# RF_And_SD_Ticketing_Master.net
KiCad netlist of a schematic drawn in Altium Designer
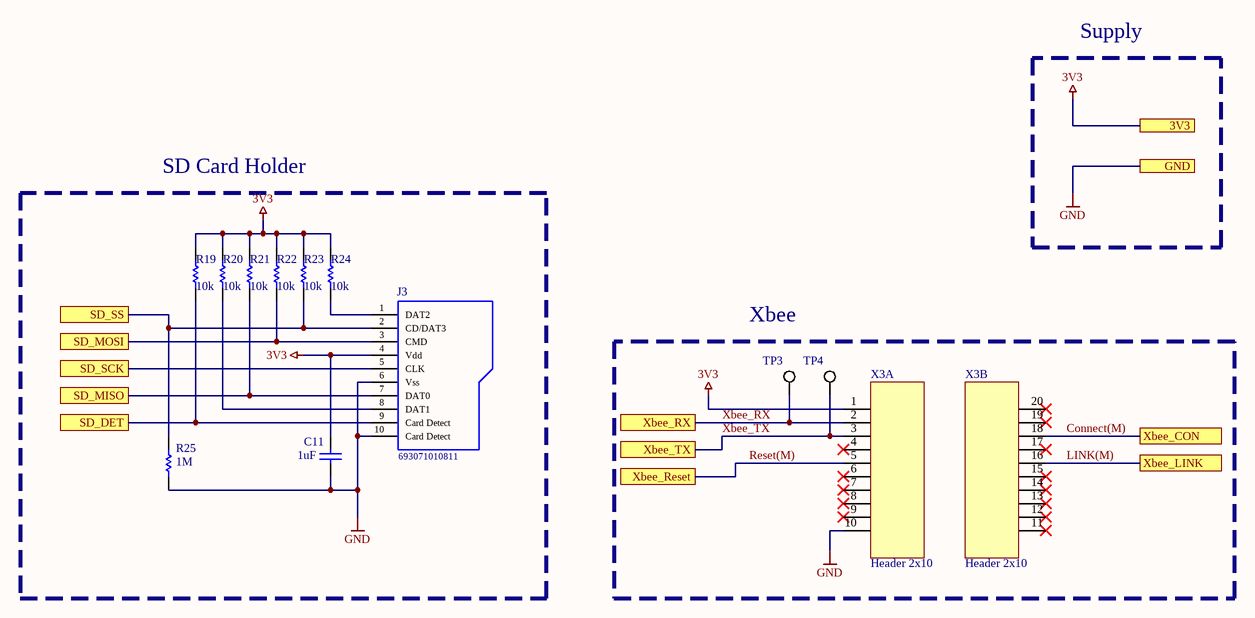
[diagram p0: RF_And_SD_Ticketing_Master.SchDoc]

(export (version "E")
  (design (tool "Eeschema 10.0.6"))
  (components
    (comp (ref "C11")
      (value "1uF")
      (footprint "6-0805_N")
      (description "Capacitor")
      (fields (field (name "PUBLISHER") "Altium Limited"))
      (libsource (lib "Miscellaneous Devices") (part "Cap"))
    )
    (comp (ref "J3")
      (value "693071010811")
      (footprint "693071010811")
      (description "WR-CRD Micro SD Card Connector, Push & Push, with card detection")
      (fields (field (name "PART NUMBER") "732-3819-1-ND") (field (name "PUBLISHER") "Wurth Elektronik"))
      (libsource (lib "ALTIUM-WR-CRD-rev18a") (part "693071010811"))
    )
    (comp (ref "R19")
      (value "10k")
      (footprint "RESC0805(2012)_L")
      (description "100K 0.125W 5% 0805 (2012 Metric)  SMD")
      (fields (field (name "TOLERANCE") "5 %") (field (name "POWER") "0.125 W"))
      (libsource (lib "Altium Content Vault") (part "CMP-1013-00122-1"))
    )
    (comp (ref "R20")
      (value "10k")
      (footprint "RESC0805(2012)_L")
      (description "100K 0.125W 5% 0805 (2012 Metric)  SMD")
      (fields (field (name "TOLERANCE") "5 %") (field (name "POWER") "0.125 W"))
      (libsource (lib "Altium Content Vault") (part "CMP-1013-00122-1"))
    )
    (comp (ref "R21")
      (value "10k")
      (footprint "RESC0805(2012)_L")
      (description "100K 0.125W 5% 0805 (2012 Metric)  SMD")
      (fields (field (name "TOLERANCE") "5 %") (field (name "POWER") "0.125 W"))
      (libsource (lib "Altium Content Vault") (part "CMP-1013-00122-1"))
    )
    (comp (ref "R22")
      (value "10k")
      (footprint "RESC0805(2012)_L")
      (description "100K 0.125W 5% 0805 (2012 Metric)  SMD")
      (fields (field (name "TOLERANCE") "5 %") (field (name "POWER") "0.125 W"))
      (libsource (lib "Altium Content Vault") (part "CMP-1013-00122-1"))
    )
    (comp (ref "R23")
      (value "10k")
      (footprint "RESC0805(2012)_L")
      (description "100K 0.125W 5% 0805 (2012 Metric)  SMD")
      (fields (field (name "TOLERANCE") "5 %") (field (name "POWER") "0.125 W"))
      (libsource (lib "Altium Content Vault") (part "CMP-1013-00122-1"))
    )
    (comp (ref "R24")
      (value "10k")
      (footprint "RESC0805(2012)_L")
      (description "100K 0.125W 5% 0805 (2012 Metric)  SMD")
      (fields (field (name "TOLERANCE") "5 %") (field (name "POWER") "0.125 W"))
      (libsource (lib "Altium Content Vault") (part "CMP-1013-00122-1"))
    )
    (comp (ref "R25")
      (value "1M")
      (footprint "RESC0805(2012)_L")
      (description "100K 0.125W 5% 0805 (2012 Metric)  SMD")
      (fields (field (name "TOLERANCE") "5 %") (field (name "POWER") "0.125 W"))
      (libsource (lib "Altium Content Vault") (part "CMP-1013-00122-1"))
    )
    (comp (ref "TP3")
      (value "~")
      (footprint "KSTN-5019_V")
      (description "Test Point, 1 Position SMD, RoHS, Tape and Reel")
      (libsource (lib "Altium Content Vault") (part "TESTPOINT_WHITE"))
    )
    (comp (ref "TP4")
      (value "~")
      (footprint "KSTN-5019_V")
      (description "Test Point, 1 Position SMD, RoHS, Tape and Reel")
      (libsource (lib "Altium Content Vault") (part "TESTPOINT_WHITE"))
    )
    (comp (ref "X3")
      (value "Header 2x10")
      (footprint "ZB-SB")
      (description "Header 2x10\r\nXbee de letml(1623) ou xbee XB24CAUIT-001")
      (libsource (lib "PCB_Ticketing_Master") (part "HDR ZB-SB 2x10_1"))
    )
  )
  (nets
    (net (code "1") (name "/Connect(M)") (class "Default") (node (ref "X3") (pin "18") (pintype "passive")))
    (net (code "2") (name "/LINK(M)") (class "Default") (node (ref "X3") (pin "16") (pintype "passive")))
    (net (code "3") (name "/Reset(M)") (class "Default") (node (ref "X3") (pin "5") (pintype "passive")))
    (net (code "4") (name "/SD_DET") (class "Default")
      (node (ref "J3") (pin "9") (pinfunction "Card_Detect_9") (pintype "passive"))
      (node (ref "R19") (pin "1") (pinfunction "1_1") (pintype "passive"))
    )
    (net (code "5") (name "/SD_MISO") (class "Default")
      (node (ref "J3") (pin "7") (pinfunction "DAT0_7") (pintype "passive"))
      (node (ref "R21") (pin "1") (pinfunction "1_1") (pintype "passive"))
    )
    (net (code "6") (name "/SD_MOSI") (class "Default")
      (node (ref "J3") (pin "3") (pinfunction "CMD_3") (pintype "passive"))
      (node (ref "R22") (pin "1") (pinfunction "1_1") (pintype "passive"))
    )
    (net (code "7") (name "/SD_SCK") (class "Default")
      (node (ref "J3") (pin "5") (pinfunction "CLK_5") (pintype "passive"))
    )
    (net (code "8") (name "/SD_SS") (class "Default")
      (node (ref "J3") (pin "2") (pinfunction "CD/DAT3_2") (pintype "passive"))
      (node (ref "R23") (pin "1") (pinfunction "1_1") (pintype "passive"))
      (node (ref "R25") (pin "2") (pinfunction "2_2") (pintype "passive"))
    )
    (net (code "9") (name "/Xbee_RX") (class "Default")
      (node (ref "TP3") (pin "1") (pinfunction "1_1") (pintype "passive"))
      (node (ref "X3") (pin "2") (pintype "passive"))
    )
    (net (code "10") (name "/Xbee_TX") (class "Default")
      (node (ref "TP4") (pin "1") (pinfunction "1_1") (pintype "passive"))
      (node (ref "X3") (pin "3") (pintype "passive"))
    )
    (net (code "11") (name "3V3") (class "Default")
      (node (ref "C11") (pin "2") (pinfunction "2_2") (pintype "passive"))
      (node (ref "J3") (pin "4") (pinfunction "Vdd_4") (pintype "passive"))
      (node (ref "R19") (pin "2") (pinfunction "2_2") (pintype "passive"))
      (node (ref "R20") (pin "2") (pinfunction "2_2") (pintype "passive"))
      (node (ref "R21") (pin "2") (pinfunction "2_2") (pintype "passive"))
      (node (ref "R22") (pin "2") (pinfunction "2_2") (pintype "passive"))
      (node (ref "R23") (pin "2") (pinfunction "2_2") (pintype "passive"))
      (node (ref "R24") (pin "2") (pinfunction "2_2") (pintype "passive"))
      (node (ref "X3") (pin "1") (pintype "passive"))
    )
    (net (code "12") (name "GND") (class "Default")
      (node (ref "C11") (pin "1") (pinfunction "1_1") (pintype "passive"))
      (node (ref "J3") (pin "10") (pinfunction "Card_Detect_10") (pintype "passive"))
      (node (ref "J3") (pin "6") (pinfunction "Vss_6") (pintype "passive"))
      (node (ref "R25") (pin "1") (pinfunction "1_1") (pintype "passive"))
      (node (ref "X3") (pin "10") (pintype "passive"))
    )
    (net (code "13") (name "Net-(J3-DAT1)") (class "Default")
      (node (ref "J3") (pin "8") (pinfunction "DAT1_8") (pintype "passive"))
      (node (ref "R20") (pin "1") (pinfunction "1_1") (pintype "passive"))
    )
    (net (code "14") (name "Net-(J3-DAT2)") (class "Default")
      (node (ref "J3") (pin "1") (pinfunction "DAT2_1") (pintype "passive"))
      (node (ref "R24") (pin "1") (pinfunction "1_1") (pintype "passive"))
    )
    (net (code "15") (name "unconnected-(X3-Pad4)") (class "Default")
      (node (ref "X3") (pin "4") (pintype "passive+no_connect"))
    )
    (net (code "16") (name "unconnected-(X3-Pad6)") (class "Default")
      (node (ref "X3") (pin "6") (pintype "passive+no_connect"))
    )
    (net (code "17") (name "unconnected-(X3-Pad7)") (class "Default")
      (node (ref "X3") (pin "7") (pintype "passive+no_connect"))
    )
    (net (code "18") (name "unconnected-(X3-Pad8)") (class "Default")
      (node (ref "X3") (pin "8") (pintype "passive+no_connect"))
    )
    (net (code "19") (name "unconnected-(X3-Pad9)") (class "Default")
      (node (ref "X3") (pin "9") (pintype "passive+no_connect"))
    )
    (net (code "20") (name "unconnected-(X3-Pad11)") (class "Default")
      (node (ref "X3") (pin "11") (pintype "passive+no_connect"))
    )
    (net (code "21") (name "unconnected-(X3-Pad12)") (class "Default")
      (node (ref "X3") (pin "12") (pintype "passive+no_connect"))
    )
    (net (code "22") (name "unconnected-(X3-Pad13)") (class "Default")
      (node (ref "X3") (pin "13") (pintype "passive+no_connect"))
    )
    (net (code "23") (name "unconnected-(X3-Pad14)") (class "Default")
      (node (ref "X3") (pin "14") (pintype "passive+no_connect"))
    )
    (net (code "24") (name "unconnected-(X3-Pad15)") (class "Default")
      (node (ref "X3") (pin "15") (pintype "passive+no_connect"))
    )
    (net (code "25") (name "unconnected-(X3-Pad17)") (class "Default")
      (node (ref "X3") (pin "17") (pintype "passive+no_connect"))
    )
    (net (code "26") (name "unconnected-(X3-Pad19)") (class "Default")
      (node (ref "X3") (pin "19") (pintype "passive+no_connect"))
    )
    (net (code "27") (name "unconnected-(X3-Pad20)") (class "Default")
      (node (ref "X3") (pin "20") (pintype "passive+no_connect"))
    )
  )
)
